# Robot_Controller.net
KiCad netlist of a schematic drawn in EAGLE
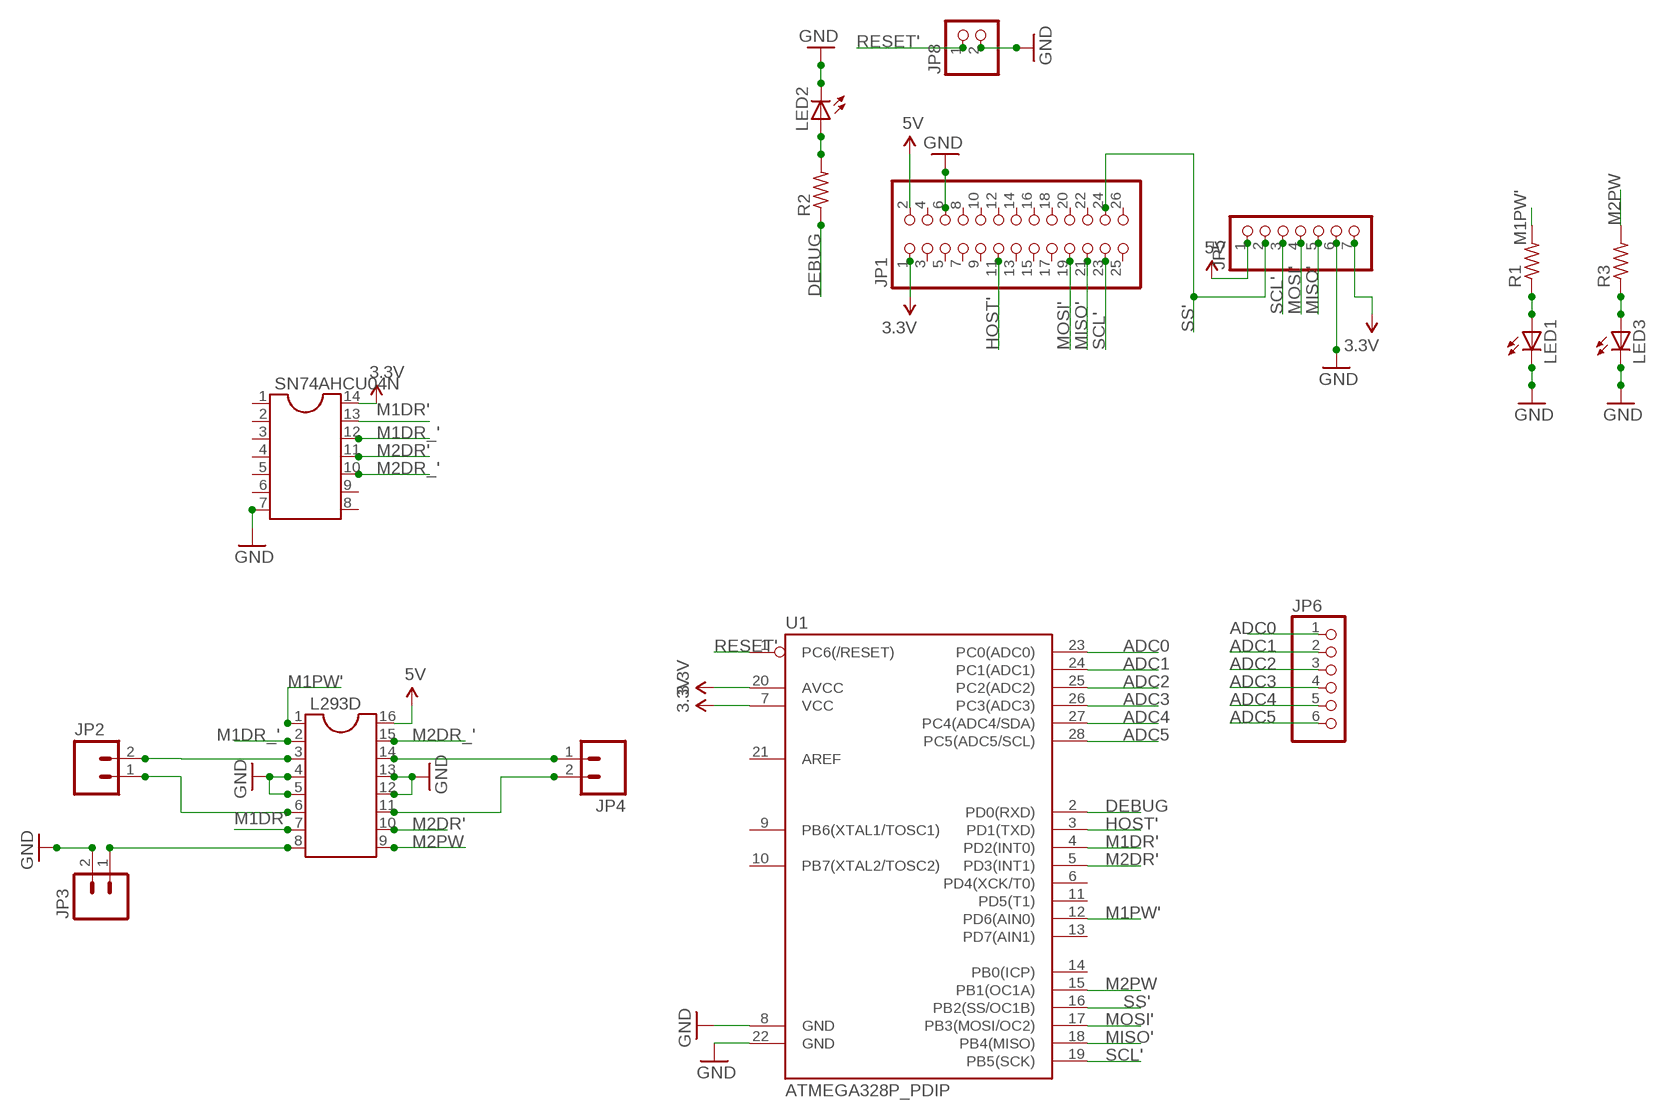
[diagram p0: schematic, sheet 1]

(export (version "E")
  (design (tool "Eeschema 10.0.6"))
  (components
    (comp (ref "JP1")
      (value "PINHD-2X13")
      (footprint "eagle-import:2X13")
      (libsource (lib "eagle-import") (part "PINHD-2X13"))
    )
    (comp (ref "JP2")
      (value "M025MM")
      (footprint "eagle-import:SCREWTERMINAL-5MM-2")
      (libsource (lib "eagle-import") (part "M025MM"))
    )
    (comp (ref "JP3")
      (value "M025MM")
      (footprint "eagle-import:SCREWTERMINAL-5MM-2")
      (libsource (lib "eagle-import") (part "M025MM"))
    )
    (comp (ref "JP4")
      (value "M025MM")
      (footprint "eagle-import:SCREWTERMINAL-5MM-2")
      (libsource (lib "eagle-import") (part "M025MM"))
    )
    (comp (ref "JP5")
      (value "PINHD-1X7")
      (footprint "eagle-import:1X07")
      (libsource (lib "eagle-import") (part "PINHD-1X7"))
    )
    (comp (ref "JP6")
      (value "PINHD-1X6")
      (footprint "eagle-import:1X06")
      (libsource (lib "eagle-import") (part "PINHD-1X6"))
    )
    (comp (ref "JP8")
      (value "PINHD-1X2")
      (footprint "eagle-import:1X02")
      (libsource (lib "eagle-import") (part "PINHD-1X2"))
    )
    (comp (ref "L293D")
      (value "DIL16S")
      (footprint "eagle-import:SOCKET-16")
      (libsource (lib "eagle-import") (part "DIL16S"))
    )
    (comp (ref "LED1")
      (value "LEDSMT1206")
      (footprint "eagle-import:1206")
      (libsource (lib "eagle-import") (part "LEDSMT1206"))
    )
    (comp (ref "LED2")
      (value "LEDSMT1206")
      (footprint "eagle-import:1206")
      (libsource (lib "eagle-import") (part "LEDSMT1206"))
    )
    (comp (ref "LED3")
      (value "LEDSMT1206")
      (footprint "eagle-import:1206")
      (libsource (lib "eagle-import") (part "LEDSMT1206"))
    )
    (comp (ref "R1")
      (value "R-US_R3216")
      (footprint "eagle-import:R3216")
      (libsource (lib "eagle-import") (part "R-US_R3216"))
    )
    (comp (ref "R2")
      (value "R-US_R3216")
      (footprint "eagle-import:R3216")
      (libsource (lib "eagle-import") (part "R-US_R3216"))
    )
    (comp (ref "R3")
      (value "R-US_R3216")
      (footprint "eagle-import:R3216")
      (libsource (lib "eagle-import") (part "R-US_R3216"))
    )
    (comp (ref "SN74AHCU04N")
      (value "DIL14S")
      (footprint "eagle-import:SOCKET-14")
      (libsource (lib "eagle-import") (part "DIL14S"))
    )
    (comp (ref "U1")
      (value "ATMEGA328P_PDIP")
      (footprint "eagle-import:DIL28-3")
      (libsource (lib "eagle-import") (part "ATMEGA328P_PDIP"))
    )
  )
  (nets
    (net (code "1") (name "/ADC0") (class "Default")
      (node (ref "JP6") (pin "1") (pinfunction "1_1") (pintype "passive"))
      (node (ref "U1") (pin "23") (pinfunction "PC0(ADC0)_23") (pintype "bidirectional"))
    )
    (net (code "2") (name "/ADC1") (class "Default")
      (node (ref "JP6") (pin "2") (pinfunction "2_2") (pintype "passive"))
      (node (ref "U1") (pin "24") (pinfunction "PC1(ADC1)_24") (pintype "bidirectional"))
    )
    (net (code "3") (name "/ADC2") (class "Default")
      (node (ref "JP6") (pin "3") (pinfunction "3_3") (pintype "passive"))
      (node (ref "U1") (pin "25") (pinfunction "PC2(ADC2)_25") (pintype "bidirectional"))
    )
    (net (code "4") (name "/ADC3") (class "Default")
      (node (ref "JP6") (pin "4") (pinfunction "4_4") (pintype "passive"))
      (node (ref "U1") (pin "26") (pinfunction "PC3(ADC3)_26") (pintype "bidirectional"))
    )
    (net (code "5") (name "/ADC4") (class "Default")
      (node (ref "JP6") (pin "5") (pinfunction "5_5") (pintype "passive"))
      (node (ref "U1") (pin "27") (pinfunction "PC4(ADC4/SDA)_27") (pintype "bidirectional"))
    )
    (net (code "6") (name "/ADC5") (class "Default")
      (node (ref "JP6") (pin "6") (pinfunction "6_6") (pintype "passive"))
      (node (ref "U1") (pin "28") (pinfunction "PC5(ADC5/SCL)_28") (pintype "bidirectional"))
    )
    (net (code "7") (name "/DEBUG") (class "Default")
      (node (ref "R2") (pin "1") (pinfunction "1_1") (pintype "passive"))
      (node (ref "U1") (pin "2") (pinfunction "PD0(RXD)_2") (pintype "bidirectional"))
    )
    (net (code "8") (name "/HOST'") (class "Default")
      (node (ref "JP1") (pin "11") (pinfunction "11_11") (pintype "passive"))
      (node (ref "U1") (pin "3") (pinfunction "PD1(TXD)_3") (pintype "bidirectional"))
    )
    (net (code "9") (name "/M1DR'") (class "Default")
      (node (ref "L293D") (pin "7") (pinfunction "7_7") (pintype "passive"))
      (node (ref "SN74AHCU04N") (pin "13") (pinfunction "13_13") (pintype "passive"))
      (node (ref "U1") (pin "4") (pinfunction "PD2(INT0)_4") (pintype "bidirectional"))
    )
    (net (code "10") (name "/M1DR_'") (class "Default")
      (node (ref "L293D") (pin "2") (pinfunction "2_2") (pintype "passive"))
      (node (ref "SN74AHCU04N") (pin "12") (pinfunction "12_12") (pintype "passive"))
    )
    (net (code "11") (name "/M1PW'") (class "Default")
      (node (ref "L293D") (pin "1") (pinfunction "1_1") (pintype "passive"))
      (node (ref "R1") (pin "2") (pinfunction "2_2") (pintype "passive"))
      (node (ref "U1") (pin "12") (pinfunction "PD6(AIN0)_12") (pintype "bidirectional"))
    )
    (net (code "12") (name "/M2DR'") (class "Default")
      (node (ref "L293D") (pin "10") (pinfunction "10_10") (pintype "passive"))
      (node (ref "SN74AHCU04N") (pin "11") (pinfunction "11_11") (pintype "passive"))
      (node (ref "U1") (pin "5") (pinfunction "PD3(INT1)_5") (pintype "bidirectional"))
    )
    (net (code "13") (name "/M2DR_'") (class "Default")
      (node (ref "L293D") (pin "15") (pinfunction "15_15") (pintype "passive"))
      (node (ref "SN74AHCU04N") (pin "10") (pinfunction "10_10") (pintype "passive"))
    )
    (net (code "14") (name "/M2PW") (class "Default")
      (node (ref "L293D") (pin "9") (pinfunction "9_9") (pintype "passive"))
      (node (ref "R3") (pin "2") (pinfunction "2_2") (pintype "passive"))
      (node (ref "U1") (pin "15") (pinfunction "PB1(OC1A)_15") (pintype "bidirectional"))
    )
    (net (code "15") (name "/MISO'") (class "Default")
      (node (ref "JP1") (pin "21") (pinfunction "21_21") (pintype "passive"))
      (node (ref "JP5") (pin "5") (pinfunction "5_5") (pintype "passive"))
      (node (ref "U1") (pin "18") (pinfunction "PB4(MISO)_18") (pintype "bidirectional"))
    )
    (net (code "16") (name "/MOSI'") (class "Default")
      (node (ref "JP1") (pin "19") (pinfunction "19_19") (pintype "passive"))
      (node (ref "JP5") (pin "4") (pinfunction "4_4") (pintype "passive"))
      (node (ref "U1") (pin "17") (pinfunction "PB3(MOSI/OC2)_17") (pintype "bidirectional"))
    )
    (net (code "17") (name "/RESET'") (class "Default")
      (node (ref "JP8") (pin "1") (pinfunction "1_1") (pintype "passive"))
      (node (ref "U1") (pin "1") (pinfunction "PC6(/RESET)_1") (pintype "bidirectional"))
    )
    (net (code "18") (name "/SCL'") (class "Default")
      (node (ref "JP1") (pin "23") (pinfunction "23_23") (pintype "passive"))
      (node (ref "JP5") (pin "3") (pinfunction "3_3") (pintype "passive"))
      (node (ref "U1") (pin "19") (pinfunction "PB5(SCK)_19") (pintype "bidirectional"))
    )
    (net (code "19") (name "/SS'") (class "Default")
      (node (ref "JP1") (pin "24") (pinfunction "24_24") (pintype "passive"))
      (node (ref "JP5") (pin "2") (pinfunction "2_2") (pintype "passive"))
      (node (ref "U1") (pin "16") (pinfunction "PB2(SS/OC1B)_16") (pintype "bidirectional"))
    )
    (net (code "20") (name "3.3V") (class "Default")
      (node (ref "JP1") (pin "1") (pinfunction "1_1") (pintype "passive"))
      (node (ref "JP5") (pin "7") (pinfunction "7_7") (pintype "passive"))
      (node (ref "SN74AHCU04N") (pin "14") (pinfunction "14_14") (pintype "passive"))
      (node (ref "U1") (pin "20") (pinfunction "AVCC_20") (pintype "bidirectional"))
      (node (ref "U1") (pin "7") (pinfunction "VCC_7") (pintype "bidirectional"))
    )
    (net (code "21") (name "5V") (class "Default")
      (node (ref "JP1") (pin "2") (pinfunction "2_2") (pintype "passive"))
      (node (ref "JP5") (pin "1") (pinfunction "1_1") (pintype "passive"))
      (node (ref "L293D") (pin "16") (pinfunction "16_16") (pintype "passive"))
    )
    (net (code "22") (name "GND") (class "Default")
      (node (ref "JP1") (pin "6") (pinfunction "6_6") (pintype "passive"))
      (node (ref "JP3") (pin "2") (pinfunction "2_2") (pintype "passive"))
      (node (ref "JP5") (pin "6") (pinfunction "6_6") (pintype "passive"))
      (node (ref "JP8") (pin "2") (pinfunction "2_2") (pintype "passive"))
      (node (ref "L293D") (pin "12") (pinfunction "12_12") (pintype "passive"))
      (node (ref "L293D") (pin "13") (pinfunction "13_13") (pintype "passive"))
      (node (ref "L293D") (pin "4") (pinfunction "4_4") (pintype "passive"))
      (node (ref "L293D") (pin "5") (pinfunction "5_5") (pintype "passive"))
      (node (ref "LED1") (pin "C") (pinfunction "C_C") (pintype "passive"))
      (node (ref "LED2") (pin "C") (pinfunction "C_C") (pintype "passive"))
      (node (ref "LED3") (pin "C") (pinfunction "C_C") (pintype "passive"))
      (node (ref "SN74AHCU04N") (pin "7") (pinfunction "7_7") (pintype "passive"))
      (node (ref "U1") (pin "22") (pinfunction "GND_22") (pintype "bidirectional"))
      (node (ref "U1") (pin "8") (pinfunction "GND_8") (pintype "bidirectional"))
    )
    (net (code "23") (name "Net-(JP2-Pad1)") (class "Default")
      (node (ref "JP2") (pin "1") (pinfunction "1_1") (pintype "passive"))
      (node (ref "L293D") (pin "6") (pinfunction "6_6") (pintype "passive"))
    )
    (net (code "24") (name "Net-(JP2-Pad2)") (class "Default")
      (node (ref "JP2") (pin "2") (pinfunction "2_2") (pintype "passive"))
      (node (ref "L293D") (pin "3") (pinfunction "3_3") (pintype "passive"))
    )
    (net (code "25") (name "Net-(JP3-Pad1)") (class "Default")
      (node (ref "JP3") (pin "1") (pinfunction "1_1") (pintype "passive"))
      (node (ref "L293D") (pin "8") (pinfunction "8_8") (pintype "passive"))
    )
    (net (code "26") (name "Net-(JP4-Pad1)") (class "Default")
      (node (ref "JP4") (pin "1") (pinfunction "1_1") (pintype "passive"))
      (node (ref "L293D") (pin "14") (pinfunction "14_14") (pintype "passive"))
    )
    (net (code "27") (name "Net-(JP4-Pad2)") (class "Default")
      (node (ref "JP4") (pin "2") (pinfunction "2_2") (pintype "passive"))
      (node (ref "L293D") (pin "11") (pinfunction "11_11") (pintype "passive"))
    )
    (net (code "28") (name "Net-(LED1-PadA)") (class "Default")
      (node (ref "LED1") (pin "A") (pinfunction "A_A") (pintype "passive"))
      (node (ref "R1") (pin "1") (pinfunction "1_1") (pintype "passive"))
    )
    (net (code "29") (name "Net-(LED2-PadA)") (class "Default")
      (node (ref "LED2") (pin "A") (pinfunction "A_A") (pintype "passive"))
      (node (ref "R2") (pin "2") (pinfunction "2_2") (pintype "passive"))
    )
    (net (code "30") (name "Net-(LED3-PadA)") (class "Default")
      (node (ref "LED3") (pin "A") (pinfunction "A_A") (pintype "passive"))
      (node (ref "R3") (pin "1") (pinfunction "1_1") (pintype "passive"))
    )
    (net (code "31") (name "unconnected-(JP1-Pad3)") (class "Default")
      (node (ref "JP1") (pin "3") (pinfunction "3_3") (pintype "passive"))
    )
    (net (code "32") (name "unconnected-(JP1-Pad4)") (class "Default")
      (node (ref "JP1") (pin "4") (pinfunction "4_4") (pintype "passive"))
    )
    (net (code "33") (name "unconnected-(JP1-Pad5)") (class "Default")
      (node (ref "JP1") (pin "5") (pinfunction "5_5") (pintype "passive"))
    )
    (net (code "34") (name "unconnected-(JP1-Pad7)") (class "Default")
      (node (ref "JP1") (pin "7") (pinfunction "7_7") (pintype "passive"))
    )
    (net (code "35") (name "unconnected-(JP1-Pad8)") (class "Default")
      (node (ref "JP1") (pin "8") (pinfunction "8_8") (pintype "passive"))
    )
    (net (code "36") (name "unconnected-(JP1-Pad9)") (class "Default")
      (node (ref "JP1") (pin "9") (pinfunction "9_9") (pintype "passive"))
    )
    (net (code "37") (name "unconnected-(JP1-Pad10)") (class "Default")
      (node (ref "JP1") (pin "10") (pinfunction "10_10") (pintype "passive"))
    )
    (net (code "38") (name "unconnected-(JP1-Pad12)") (class "Default")
      (node (ref "JP1") (pin "12") (pinfunction "12_12") (pintype "passive"))
    )
    (net (code "39") (name "unconnected-(JP1-Pad13)") (class "Default")
      (node (ref "JP1") (pin "13") (pinfunction "13_13") (pintype "passive"))
    )
    (net (code "40") (name "unconnected-(JP1-Pad14)") (class "Default")
      (node (ref "JP1") (pin "14") (pinfunction "14_14") (pintype "passive"))
    )
    (net (code "41") (name "unconnected-(JP1-Pad15)") (class "Default")
      (node (ref "JP1") (pin "15") (pinfunction "15_15") (pintype "passive"))
    )
    (net (code "42") (name "unconnected-(JP1-Pad16)") (class "Default")
      (node (ref "JP1") (pin "16") (pinfunction "16_16") (pintype "passive"))
    )
    (net (code "43") (name "unconnected-(JP1-Pad17)") (class "Default")
      (node (ref "JP1") (pin "17") (pinfunction "17_17") (pintype "passive"))
    )
    (net (code "44") (name "unconnected-(JP1-Pad18)") (class "Default")
      (node (ref "JP1") (pin "18") (pinfunction "18_18") (pintype "passive"))
    )
    (net (code "45") (name "unconnected-(JP1-Pad20)") (class "Default")
      (node (ref "JP1") (pin "20") (pinfunction "20_20") (pintype "passive"))
    )
    (net (code "46") (name "unconnected-(JP1-Pad22)") (class "Default")
      (node (ref "JP1") (pin "22") (pinfunction "22_22") (pintype "passive"))
    )
    (net (code "47") (name "unconnected-(JP1-Pad25)") (class "Default")
      (node (ref "JP1") (pin "25") (pinfunction "25_25") (pintype "passive"))
    )
    (net (code "48") (name "unconnected-(JP1-Pad26)") (class "Default")
      (node (ref "JP1") (pin "26") (pinfunction "26_26") (pintype "passive"))
    )
    (net (code "49") (name "unconnected-(SN74AHCU04N-Pad1)") (class "Default")
      (node (ref "SN74AHCU04N") (pin "1") (pinfunction "1_1") (pintype "passive"))
    )
    (net (code "50") (name "unconnected-(SN74AHCU04N-Pad2)") (class "Default")
      (node (ref "SN74AHCU04N") (pin "2") (pinfunction "2_2") (pintype "passive"))
    )
    (net (code "51") (name "unconnected-(SN74AHCU04N-Pad3)") (class "Default")
      (node (ref "SN74AHCU04N") (pin "3") (pinfunction "3_3") (pintype "passive"))
    )
    (net (code "52") (name "unconnected-(SN74AHCU04N-Pad4)") (class "Default")
      (node (ref "SN74AHCU04N") (pin "4") (pinfunction "4_4") (pintype "passive"))
    )
    (net (code "53") (name "unconnected-(SN74AHCU04N-Pad5)") (class "Default")
      (node (ref "SN74AHCU04N") (pin "5") (pinfunction "5_5") (pintype "passive"))
    )
    (net (code "54") (name "unconnected-(SN74AHCU04N-Pad6)") (class "Default")
      (node (ref "SN74AHCU04N") (pin "6") (pinfunction "6_6") (pintype "passive"))
    )
    (net (code "55") (name "unconnected-(SN74AHCU04N-Pad8)") (class "Default")
      (node (ref "SN74AHCU04N") (pin "8") (pinfunction "8_8") (pintype "passive"))
    )
    (net (code "56") (name "unconnected-(SN74AHCU04N-Pad9)") (class "Default")
      (node (ref "SN74AHCU04N") (pin "9") (pinfunction "9_9") (pintype "passive"))
    )
    (net (code "57") (name "unconnected-(U1-AREF-Pad21)") (class "Default")
      (node (ref "U1") (pin "21") (pinfunction "AREF_21") (pintype "bidirectional"))
    )
    (net (code "58") (name "unconnected-(U1-PB0(ICP)-Pad14)") (class "Default")
      (node (ref "U1") (pin "14") (pinfunction "PB0(ICP)_14") (pintype "bidirectional"))
    )
    (net (code "59") (name "unconnected-(U1-PB6(XTAL1{slash}TOSC1)-Pad9)") (class "Default")
      (node (ref "U1") (pin "9") (pinfunction "PB6(XTAL1/TOSC1)_9") (pintype "bidirectional"))
    )
    (net (code "60") (name "unconnected-(U1-PB7(XTAL2{slash}TOSC2)-Pad10)") (class "Default")
      (node (ref "U1") (pin "10") (pinfunction "PB7(XTAL2/TOSC2)_10") (pintype "bidirectional"))
    )
    (net (code "61") (name "unconnected-(U1-PD4(XCK{slash}T0)-Pad6)") (class "Default")
      (node (ref "U1") (pin "6") (pinfunction "PD4(XCK/T0)_6") (pintype "bidirectional"))
    )
    (net (code "62") (name "unconnected-(U1-PD5(T1)-Pad11)") (class "Default")
      (node (ref "U1") (pin "11") (pinfunction "PD5(T1)_11") (pintype "bidirectional"))
    )
    (net (code "63") (name "unconnected-(U1-PD7(AIN1)-Pad13)") (class "Default")
      (node (ref "U1") (pin "13") (pinfunction "PD7(AIN1)_13") (pintype "bidirectional"))
    )
  )
)
